# 02_-_PWR_1V8.net
KiCad netlist of a schematic drawn in Altium Designer
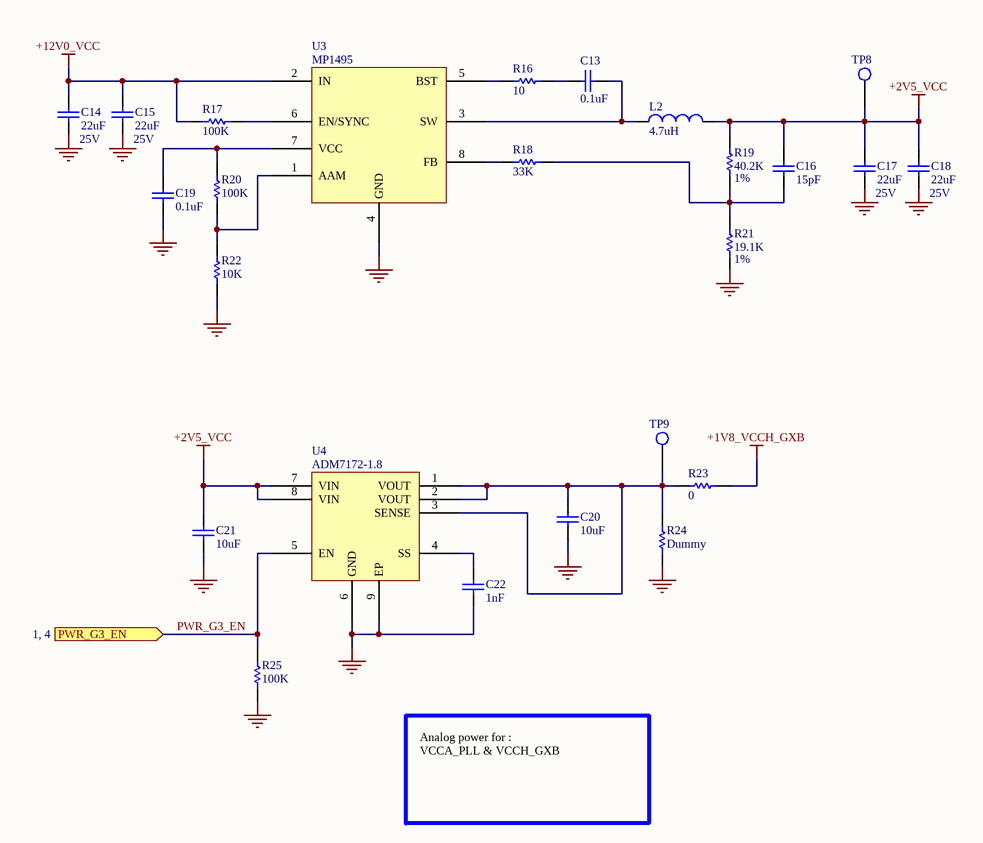
[diagram p0: [02] - PWR 1V8.SchDoc]

(export (version "E")
  (design (tool "Eeschema 10.0.6"))
  (components
    (comp (ref "C13")
      (value "0.1uF")
      (footprint "0402_C")
      (description "Non-Pol SMD Capacitor")
      (libsource (lib "Passive Components") (part "Cap SMD"))
    )
    (comp (ref "C14")
      (value "22uF")
      (footprint "1210_C")
      (description "Non-Pol SMD Capacitor")
      (fields (field (name "RATED_VOLTAGE") "25V") (field (name "MANUFACTURER PART NUM") "GRM32ER71E226KE15"))
      (libsource (lib "Passive Components") (part "Cap SMD"))
    )
    (comp (ref "C15")
      (value "22uF")
      (footprint "1210_C")
      (description "Non-Pol SMD Capacitor")
      (fields (field (name "RATED_VOLTAGE") "25V") (field (name "MANUFACTURER PART NUM") "GRM32ER71E226KE15"))
      (libsource (lib "Passive Components") (part "Cap SMD"))
    )
    (comp (ref "C16")
      (value "15pF")
      (footprint "0402_C")
      (description "Non-Pol SMD Capacitor")
      (libsource (lib "Passive Components") (part "Cap SMD"))
    )
    (comp (ref "C17")
      (value "22uF")
      (footprint "1210_C")
      (description "Non-Pol SMD Capacitor")
      (fields (field (name "RATED_VOLTAGE") "25V") (field (name "MANUFACTURER PART NUM") "GRM32ER71E226KE15"))
      (libsource (lib "Passive Components") (part "Cap SMD"))
    )
    (comp (ref "C18")
      (value "22uF")
      (footprint "1210_C")
      (description "Non-Pol SMD Capacitor")
      (fields (field (name "RATED_VOLTAGE") "25V") (field (name "MANUFACTURER PART NUM") "GRM32ER71E226KE15"))
      (libsource (lib "Passive Components") (part "Cap SMD"))
    )
    (comp (ref "C19")
      (value "0.1uF")
      (footprint "0402_C")
      (description "Non-Pol SMD Capacitor")
      (libsource (lib "Passive Components") (part "Cap SMD"))
    )
    (comp (ref "C20")
      (value "10uF")
      (footprint "0805_C")
      (description "Non-Pol SMD Capacitor")
      (fields (field (name "MANUFACTURER PART NUM") "GRM21BR71A106MA73"))
      (libsource (lib "Passive Components") (part "Cap SMD"))
    )
    (comp (ref "C21")
      (value "10uF")
      (footprint "0805_C")
      (description "Non-Pol SMD Capacitor")
      (fields (field (name "MANUFACTURER PART NUM") "GRM21BR71A106MA73"))
      (libsource (lib "Passive Components") (part "Cap SMD"))
    )
    (comp (ref "C22")
      (value "1nF")
      (footprint "0402_C")
      (description "Non-Pol SMD Capacitor")
      (libsource (lib "Passive Components") (part "Cap SMD"))
    )
    (comp (ref "L2")
      (value "4.7uH")
      (footprint "IHLP-2525")
      (description "Inductor SMD")
      (fields (field (name "MANUFACTURER PART NUM") "IHLP2525CZER4R7M01"))
      (libsource (lib "Passive Components") (part "Inductor"))
    )
    (comp (ref "R16")
      (value "10")
      (footprint "0402_R")
      (description "SMD Resistor")
      (fields (field (name "TOLERANCE") "5%"))
      (libsource (lib "Passive Components") (part "Res SMD"))
    )
    (comp (ref "R17")
      (value "100K")
      (footprint "0402_R")
      (description "SMD Resistor")
      (fields (field (name "TOLERANCE") "5%"))
      (libsource (lib "Passive Components") (part "Res SMD"))
    )
    (comp (ref "R18")
      (value "33K")
      (footprint "0402_R")
      (description "SMD Resistor")
      (fields (field (name "TOLERANCE") "5%"))
      (libsource (lib "Passive Components") (part "Res SMD"))
    )
    (comp (ref "R19")
      (value "40.2K")
      (footprint "0402_R")
      (description "SMD Resistor")
      (fields (field (name "TOLERANCE") "1%"))
      (libsource (lib "Passive Components") (part "Res SMD"))
    )
    (comp (ref "R20")
      (value "100K")
      (footprint "0402_R")
      (description "SMD Resistor")
      (fields (field (name "TOLERANCE") "5%"))
      (libsource (lib "Passive Components") (part "Res SMD"))
    )
    (comp (ref "R21")
      (value "19.1K")
      (footprint "0402_R")
      (description "SMD Resistor")
      (fields (field (name "TOLERANCE") "1%"))
      (libsource (lib "Passive Components") (part "Res SMD"))
    )
    (comp (ref "R22")
      (value "10K")
      (footprint "0402_R")
      (description "SMD Resistor")
      (fields (field (name "TOLERANCE") "5%"))
      (libsource (lib "Passive Components") (part "Res SMD"))
    )
    (comp (ref "R23")
      (value "0")
      (footprint "1210_R")
      (description "SMD Resistor")
      (fields (field (name "TOLERANCE") "5%"))
      (libsource (lib "Passive Components") (part "Res SMD"))
    )
    (comp (ref "R24")
      (value "Dummy")
      (footprint "1210_R")
      (description "SMD Resistor")
      (fields (field (name "TOLERANCE") "5%"))
      (libsource (lib "Passive Components") (part "Res SMD"))
    )
    (comp (ref "R25")
      (value "100K")
      (footprint "0402_R")
      (description "SMD Resistor")
      (fields (field (name "TOLERANCE") "5%"))
      (libsource (lib "Passive Components") (part "Res SMD"))
    )
    (comp (ref "TP8")
      (value "Test Point")
      (footprint "PIN_1.5mm")
      (description "Test Point Footprint")
      (libsource (lib "Passive Components") (part "Test Point"))
    )
    (comp (ref "TP9")
      (value "Test Point")
      (footprint "PIN_1.5mm")
      (description "Test Point Footprint")
      (libsource (lib "Passive Components") (part "Test Point"))
    )
    (comp (ref "U3")
      (value "MP1495")
      (footprint "TSOT23-8")
      (description "High Efficiency 3A, 16V, 500kHz Synchronous Step Down Converter")
      (fields (field (name "MANUFACTURER PART NUM") "MP1495SGJ-Z"))
      (libsource (lib "Project_schlib") (part "MP1495"))
    )
    (comp (ref "U4")
      (value "ADM7172-1.8")
      (description "6.5 V, 2 A, Ultralow Noise, High PSRR, Fast Transient Response CMOS LDO")
      (fields (field (name "MANUFACTURER PART NUM") "ADM7172ACPZ-1.8-R7"))
      (libsource (lib "Project_schlib") (part "ADM7172"))
    )
  )
  (nets
    (net (code "1") (name "+1V8_VCCH_GXB") (class "Default")
      (node (ref "R23") (pin "2") (pinfunction "2_2") (pintype "passive"))
    )
    (net (code "2") (name "+2V5_VCC") (class "Default")
      (node (ref "C16") (pin "2") (pinfunction "2_2") (pintype "passive"))
      (node (ref "C17") (pin "2") (pinfunction "2_2") (pintype "passive"))
      (node (ref "C18") (pin "2") (pinfunction "2_2") (pintype "passive"))
      (node (ref "C21") (pin "2") (pinfunction "2_2") (pintype "passive"))
      (node (ref "L2") (pin "2") (pinfunction "2_2") (pintype "passive"))
      (node (ref "R19") (pin "2") (pinfunction "2_2") (pintype "passive"))
      (node (ref "TP8") (pin "1") (pinfunction "1_1") (pintype "passive"))
      (node (ref "U4") (pin "7") (pinfunction "VIN_7") (pintype "power_in"))
      (node (ref "U4") (pin "8") (pinfunction "VIN_8") (pintype "power_in"))
    )
    (net (code "3") (name "+12V0_VCC") (class "Default")
      (node (ref "C14") (pin "2") (pinfunction "2_2") (pintype "passive"))
      (node (ref "C15") (pin "2") (pinfunction "2_2") (pintype "passive"))
      (node (ref "R17") (pin "2") (pinfunction "2_2") (pintype "passive"))
      (node (ref "U3") (pin "2") (pinfunction "IN_2") (pintype "passive"))
    )
    (net (code "4") (name "/PWR_G3_EN") (class "Default")
      (node (ref "R25") (pin "1") (pinfunction "1_1") (pintype "passive"))
      (node (ref "U4") (pin "5") (pinfunction "EN_5") (pintype "passive"))
    )
    (net (code "5") (name "GND") (class "Default")
      (node (ref "C14") (pin "1") (pinfunction "1_1") (pintype "passive"))
      (node (ref "C15") (pin "1") (pinfunction "1_1") (pintype "passive"))
      (node (ref "C17") (pin "1") (pinfunction "1_1") (pintype "passive"))
      (node (ref "C18") (pin "1") (pinfunction "1_1") (pintype "passive"))
      (node (ref "C19") (pin "1") (pinfunction "1_1") (pintype "passive"))
      (node (ref "C20") (pin "1") (pinfunction "1_1") (pintype "passive"))
      (node (ref "C21") (pin "1") (pinfunction "1_1") (pintype "passive"))
      (node (ref "C22") (pin "1") (pinfunction "1_1") (pintype "passive"))
      (node (ref "R21") (pin "1") (pinfunction "1_1") (pintype "passive"))
      (node (ref "R22") (pin "1") (pinfunction "1_1") (pintype "passive"))
      (node (ref "R24") (pin "1") (pinfunction "1_1") (pintype "passive"))
      (node (ref "R25") (pin "2") (pinfunction "2_2") (pintype "passive"))
      (node (ref "U3") (pin "4") (pinfunction "GND_4") (pintype "passive"))
      (node (ref "U4") (pin "6") (pinfunction "GND_6") (pintype "power_in"))
      (node (ref "U4") (pin "9") (pinfunction "EP_9") (pintype "power_in"))
    )
    (net (code "6") (name "Net-(C13-Pad1)") (class "Default")
      (node (ref "C13") (pin "1") (pinfunction "1_1") (pintype "passive"))
      (node (ref "R16") (pin "2") (pinfunction "2_2") (pintype "passive"))
    )
    (net (code "7") (name "Net-(C16-Pad1)") (class "Default")
      (node (ref "C16") (pin "1") (pinfunction "1_1") (pintype "passive"))
      (node (ref "R18") (pin "2") (pinfunction "2_2") (pintype "passive"))
      (node (ref "R19") (pin "1") (pinfunction "1_1") (pintype "passive"))
      (node (ref "R21") (pin "2") (pinfunction "2_2") (pintype "passive"))
    )
    (net (code "8") (name "Net-(U3-AAM)") (class "Default")
      (node (ref "R20") (pin "1") (pinfunction "1_1") (pintype "passive"))
      (node (ref "R22") (pin "2") (pinfunction "2_2") (pintype "passive"))
      (node (ref "U3") (pin "1") (pinfunction "AAM_1") (pintype "passive"))
    )
    (net (code "9") (name "Net-(U3-BST)") (class "Default")
      (node (ref "R16") (pin "1") (pinfunction "1_1") (pintype "passive"))
      (node (ref "U3") (pin "5") (pinfunction "BST_5") (pintype "passive"))
    )
    (net (code "10") (name "Net-(U3-EN{slash}SYNC)") (class "Default")
      (node (ref "R17") (pin "1") (pinfunction "1_1") (pintype "passive"))
      (node (ref "U3") (pin "6") (pinfunction "EN/SYNC_6") (pintype "passive"))
    )
    (net (code "11") (name "Net-(U3-FB)") (class "Default")
      (node (ref "R18") (pin "1") (pinfunction "1_1") (pintype "passive"))
      (node (ref "U3") (pin "8") (pinfunction "FB_8") (pintype "passive"))
    )
    (net (code "12") (name "Net-(U3-SW)") (class "Default")
      (node (ref "C13") (pin "2") (pinfunction "2_2") (pintype "passive"))
      (node (ref "L2") (pin "1") (pinfunction "1_1") (pintype "passive"))
      (node (ref "U3") (pin "3") (pinfunction "SW_3") (pintype "passive"))
    )
    (net (code "13") (name "Net-(U3-VCC)") (class "Default")
      (node (ref "C19") (pin "2") (pinfunction "2_2") (pintype "passive"))
      (node (ref "R20") (pin "2") (pinfunction "2_2") (pintype "passive"))
      (node (ref "U3") (pin "7") (pinfunction "VCC_7") (pintype "passive"))
    )
    (net (code "14") (name "Net-(U4-SENSE)") (class "Default")
      (node (ref "C20") (pin "2") (pinfunction "2_2") (pintype "passive"))
      (node (ref "R23") (pin "1") (pinfunction "1_1") (pintype "passive"))
      (node (ref "R24") (pin "2") (pinfunction "2_2") (pintype "passive"))
      (node (ref "TP9") (pin "1") (pinfunction "1_1") (pintype "passive"))
      (node (ref "U4") (pin "1") (pinfunction "VOUT_1") (pintype "power_in"))
      (node (ref "U4") (pin "2") (pinfunction "VOUT_2") (pintype "power_in"))
      (node (ref "U4") (pin "3") (pinfunction "SENSE_3") (pintype "power_in"))
    )
    (net (code "15") (name "Net-(U4-SS)") (class "Default")
      (node (ref "C22") (pin "2") (pinfunction "2_2") (pintype "passive"))
      (node (ref "U4") (pin "4") (pinfunction "SS_4") (pintype "passive"))
    )
  )
)
